# DigitalInclinometer.net
KiCad netlist of a schematic drawn in Altium Designer
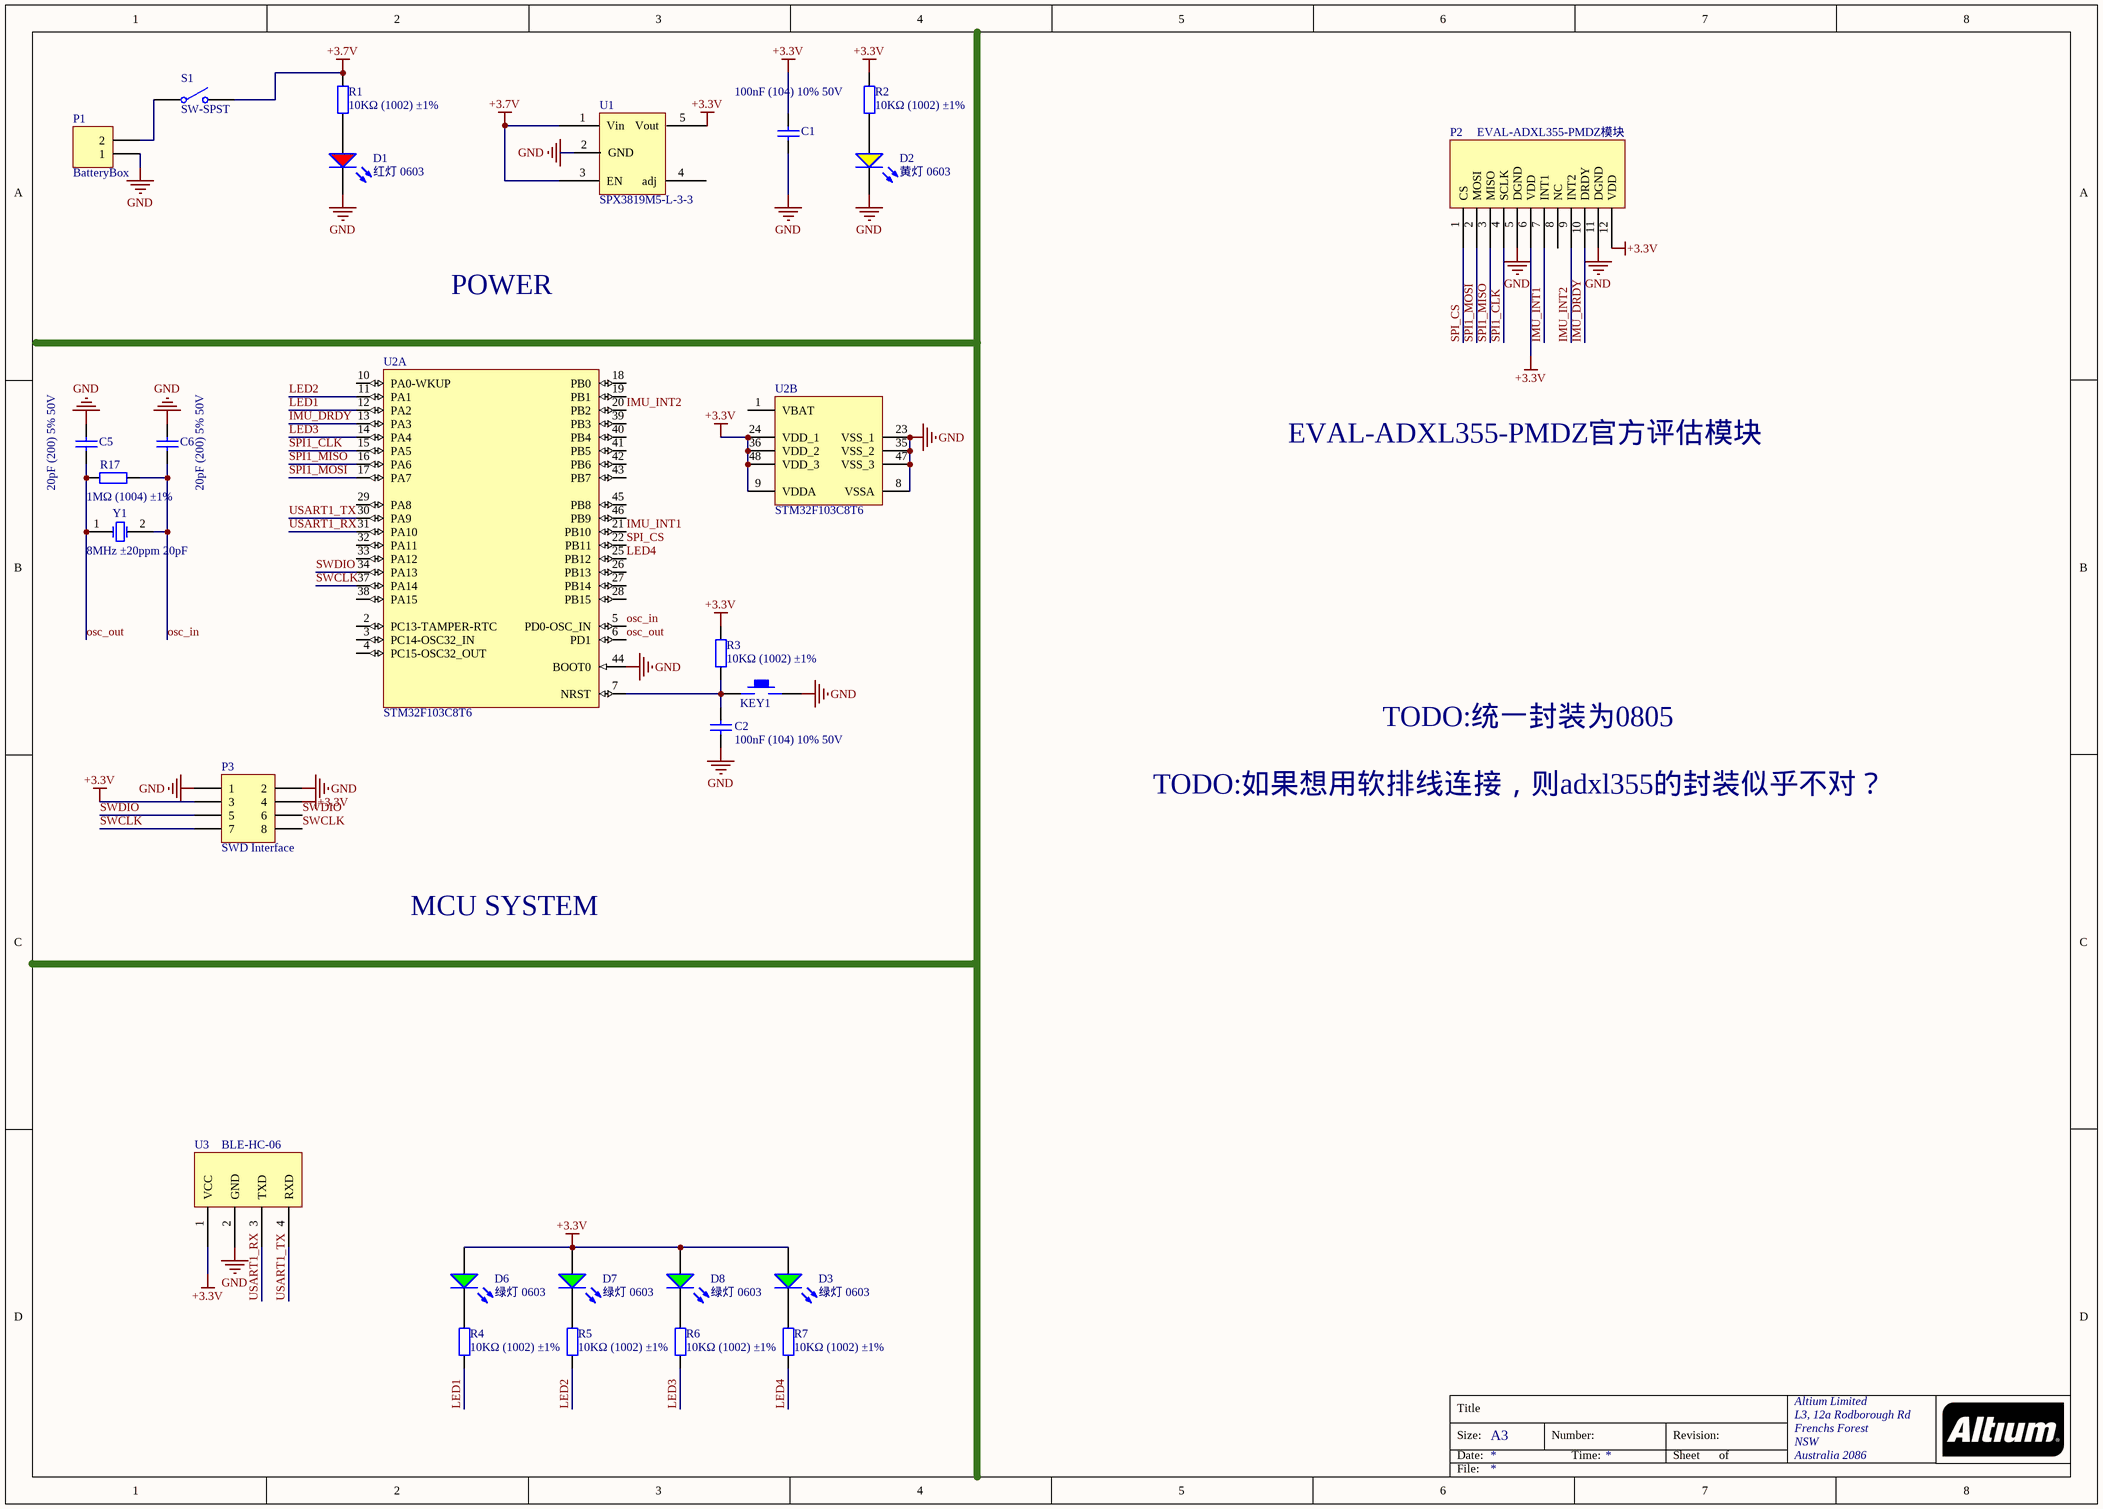
[diagram p0: DigitalInclinometer.SchDoc]

(export (version "E")
  (design (tool "Eeschema 10.0.6"))
  (components
    (comp (ref "C1")
      (value "100nF (104) 10% 50V")
      (footprint "0603_C")
      (description "贴片电容")
      (libsource (lib "Miscellaneous Devices LC") (part "0603 100nF (104) 10% 50V"))
    )
    (comp (ref "C2")
      (value "100nF (104) 10% 50V")
      (footprint "0603_C")
      (description "贴片电容")
      (libsource (lib "Miscellaneous Devices LC") (part "0603 100nF (104) 10% 50V"))
    )
    (comp (ref "C5")
      (value "20pF (200) 5% 50V")
      (footprint "0603_C")
      (description "贴片电容")
      (libsource (lib "Miscellaneous Devices LC") (part "0603 20pF (200) 5% 50V"))
    )
    (comp (ref "C6")
      (value "20pF (200) 5% 50V")
      (footprint "0603_C")
      (description "贴片电容")
      (libsource (lib "Miscellaneous Devices LC") (part "0603 20pF (200) 5% 50V"))
    )
    (comp (ref "D1")
      (value "红灯 0603")
      (footprint "0603_LED_S1")
      (description "发光二极管")
      (libsource (lib "Miscellaneous Devices LC") (part "0603 红灯"))
    )
    (comp (ref "D2")
      (value "黄灯 0603")
      (footprint "0603_LED_S1")
      (description "发光二极管")
      (libsource (lib "Miscellaneous Devices LC") (part "0603 黄灯"))
    )
    (comp (ref "D3")
      (value "绿灯 0603")
      (footprint "0603_LED_S1")
      (description "发光二极管")
      (libsource (lib "Miscellaneous Devices LC") (part "0603 绿灯"))
    )
    (comp (ref "D6")
      (value "绿灯 0603")
      (footprint "0603_LED_S1")
      (description "发光二极管")
      (libsource (lib "Miscellaneous Devices LC") (part "0603 绿灯"))
    )
    (comp (ref "D7")
      (value "绿灯 0603")
      (footprint "0603_LED_S1")
      (description "发光二极管")
      (libsource (lib "Miscellaneous Devices LC") (part "0603 绿灯"))
    )
    (comp (ref "D8")
      (value "绿灯 0603")
      (footprint "0603_LED_S1")
      (description "发光二极管")
      (libsource (lib "Miscellaneous Devices LC") (part "0603 绿灯"))
    )
    (comp (ref "KEY1")
      (value "KEY_M")
      (footprint "RESET-KEY-SMD")
      (libsource (lib "WarShip V3 STM32103封装库") (part "KEY_M"))
    )
    (comp (ref "P1")
      (value "BatteryBox")
      (footprint "14500LiBatteryBox")
      (description "Header, 2-Pin")
      (fields (field (name "PUBLISHER") "Altium Limited"))
      (libsource (lib "Miscellaneous Connectors") (part "Header 2"))
    )
    (comp (ref "P2")
      (value "EVAL-ADXL355-PMDZ模块")
      (footprint "ADXL355MODULE")
      (libsource (lib "IMU_STUDY") (part "EVAL-ADXL355-PMDZ模块"))
    )
    (comp (ref "P3")
      (value "SWD Interface")
      (footprint "2.54mmHeader2x4-SMD")
      (description "Header, 4-Pin, Dual row")
      (fields (field (name "PUBLISHER") "Altium Limited"))
      (libsource (lib "Miscellaneous Connectors") (part "Header 4X2"))
    )
    (comp (ref "R1")
      (value "10KΩ (1002) ±1%")
      (footprint "0603_R")
      (description "贴片电阻")
      (libsource (lib "Miscellaneous Devices LC") (part "0603 10KΩ (1002) 1%"))
    )
    (comp (ref "R2")
      (value "10KΩ (1002) ±1%")
      (footprint "0603_R")
      (description "贴片电阻")
      (libsource (lib "Miscellaneous Devices LC") (part "0603 10KΩ (1002) 1%"))
    )
    (comp (ref "R3")
      (value "10KΩ (1002) ±1%")
      (footprint "0603_R")
      (description "贴片电阻")
      (libsource (lib "Miscellaneous Devices LC") (part "0603 10KΩ (1002) 1%"))
    )
    (comp (ref "R4")
      (value "10KΩ (1002) ±1%")
      (footprint "0603_R")
      (description "贴片电阻")
      (libsource (lib "Miscellaneous Devices LC") (part "0603 10KΩ (1002) 1%"))
    )
    (comp (ref "R5")
      (value "10KΩ (1002) ±1%")
      (footprint "0603_R")
      (description "贴片电阻")
      (libsource (lib "Miscellaneous Devices LC") (part "0603 10KΩ (1002) 1%"))
    )
    (comp (ref "R6")
      (value "10KΩ (1002) ±1%")
      (footprint "0603_R")
      (description "贴片电阻")
      (libsource (lib "Miscellaneous Devices LC") (part "0603 10KΩ (1002) 1%"))
    )
    (comp (ref "R7")
      (value "10KΩ (1002) ±1%")
      (footprint "0603_R")
      (description "贴片电阻")
      (libsource (lib "Miscellaneous Devices LC") (part "0603 10KΩ (1002) 1%"))
    )
    (comp (ref "R17")
      (value "1MΩ (1004) ±1%")
      (footprint "0603_R")
      (description "贴片电阻")
      (libsource (lib "Miscellaneous Devices LC") (part "0603 1MΩ (1004) 1%"))
    )
    (comp (ref "S1")
      (value "SW-SPST")
      (footprint "PowerSwitcher")
      (description "Single-Pole, Single-Throw Switch")
      (fields (field (name "PUBLISHER") "Altium Limited"))
      (libsource (lib "Miscellaneous Devices") (part "SW-SPST"))
    )
    (comp (ref "U1")
      (value "SPX3819M5-L-3-3")
      (footprint "SOT-23-5")
      (libsource (lib "micro_driver_demo") (part "SPX3819M5-L-3-3"))
    )
    (comp (ref "U2")
      (value "STM32F103C8T6")
      (footprint "LQFP-48_7x7x05P")
      (description "ARM")
      (libsource (lib "Miscellaneous Devices LC") (part "STM32F103C8T6"))
    )
    (comp (ref "U3")
      (value "BLE-HC-06")
      (footprint "BLE-HC06-SMD")
      (libsource (lib "DigitalInclinometer") (part "BLE-HC-06"))
    )
    (comp (ref "Y1")
      (value "8MHz ±20ppm 20pF")
      (footprint "SMD-5032_2P")
      (description "贴片晶振")
      (libsource (lib "Miscellaneous Devices LC") (part "SMD-5032_2P 8MHz 20ppm 20pF"))
    )
  )
  (nets
    (net (code "1") (name "+3.3V") (class "Default")
      (node (ref "C1") (pin "2") (pinfunction "2_2") (pintype "passive"))
      (node (ref "D3") (pin "A") (pinfunction "A_A") (pintype "passive"))
      (node (ref "D6") (pin "A") (pinfunction "A_A") (pintype "passive"))
      (node (ref "D7") (pin "A") (pinfunction "A_A") (pintype "passive"))
      (node (ref "D8") (pin "A") (pinfunction "A_A") (pintype "passive"))
      (node (ref "P2") (pin "12") (pinfunction "VDD_12") (pintype "passive"))
      (node (ref "P2") (pin "6") (pinfunction "VDD_6") (pintype "passive"))
      (node (ref "P3") (pin "3") (pinfunction "3_3") (pintype "passive"))
      (node (ref "P3") (pin "4") (pinfunction "4_4") (pintype "passive"))
      (node (ref "R2") (pin "2") (pinfunction "2_2") (pintype "passive"))
      (node (ref "R3") (pin "2") (pinfunction "2_2") (pintype "passive"))
      (node (ref "U1") (pin "5") (pinfunction "Vout_5") (pintype "passive"))
      (node (ref "U2") (pin "24") (pinfunction "VDD_1_24") (pintype "power_in"))
      (node (ref "U2") (pin "36") (pinfunction "VDD_2_36") (pintype "power_in"))
      (node (ref "U2") (pin "48") (pinfunction "VDD_3_48") (pintype "power_in"))
      (node (ref "U2") (pin "9") (pinfunction "VDDA_9") (pintype "power_in"))
      (node (ref "U3") (pin "1") (pinfunction "VCC_1") (pintype "passive"))
    )
    (net (code "2") (name "+3.7V") (class "Default")
      (node (ref "R1") (pin "2") (pinfunction "2_2") (pintype "passive"))
      (node (ref "S1") (pin "2") (pinfunction "NO_2") (pintype "passive"))
      (node (ref "U1") (pin "1") (pinfunction "Vin_1") (pintype "passive"))
      (node (ref "U1") (pin "3") (pinfunction "EN_3") (pintype "passive"))
    )
    (net (code "3") (name "/IMU_DRDY") (class "Default")
      (node (ref "P2") (pin "10") (pinfunction "DRDY_10") (pintype "passive"))
      (node (ref "U2") (pin "13") (pinfunction "PA3_13") (pintype "bidirectional"))
    )
    (net (code "4") (name "/IMU_INT1") (class "Default")
      (node (ref "P2") (pin "7") (pinfunction "INT1_7") (pintype "passive"))
      (node (ref "U2") (pin "21") (pinfunction "PB10_21") (pintype "bidirectional"))
    )
    (net (code "5") (name "/IMU_INT2") (class "Default")
      (node (ref "P2") (pin "9") (pinfunction "INT2_9") (pintype "passive"))
      (node (ref "U2") (pin "20") (pinfunction "PB2_20") (pintype "bidirectional"))
    )
    (net (code "6") (name "/LED1") (class "Default")
      (node (ref "R4") (pin "1") (pinfunction "1_1") (pintype "passive"))
      (node (ref "U2") (pin "12") (pinfunction "PA2_12") (pintype "bidirectional"))
    )
    (net (code "7") (name "/LED2") (class "Default")
      (node (ref "R5") (pin "1") (pinfunction "1_1") (pintype "passive"))
      (node (ref "U2") (pin "11") (pinfunction "PA1_11") (pintype "bidirectional"))
    )
    (net (code "8") (name "/LED3") (class "Default")
      (node (ref "R6") (pin "1") (pinfunction "1_1") (pintype "passive"))
      (node (ref "U2") (pin "14") (pinfunction "PA4_14") (pintype "bidirectional"))
    )
    (net (code "9") (name "/LED4") (class "Default")
      (node (ref "R7") (pin "1") (pinfunction "1_1") (pintype "passive"))
      (node (ref "U2") (pin "25") (pinfunction "PB12_25") (pintype "bidirectional"))
    )
    (net (code "10") (name "/SPI1_CLK") (class "Default")
      (node (ref "P2") (pin "4") (pinfunction "SCLK_4") (pintype "passive"))
      (node (ref "U2") (pin "15") (pinfunction "PA5_15") (pintype "bidirectional"))
    )
    (net (code "11") (name "/SPI1_MISO") (class "Default")
      (node (ref "P2") (pin "3") (pinfunction "MISO_3") (pintype "passive"))
      (node (ref "U2") (pin "16") (pinfunction "PA6_16") (pintype "bidirectional"))
    )
    (net (code "12") (name "/SPI1_MOSI") (class "Default")
      (node (ref "P2") (pin "2") (pinfunction "MOSI_2") (pintype "passive"))
      (node (ref "U2") (pin "17") (pinfunction "PA7_17") (pintype "bidirectional"))
    )
    (net (code "13") (name "/SPI_CS") (class "Default")
      (node (ref "P2") (pin "1") (pinfunction "CS_1") (pintype "passive"))
      (node (ref "U2") (pin "22") (pinfunction "PB11_22") (pintype "bidirectional"))
    )
    (net (code "14") (name "/SWCLK") (class "Default")
      (node (ref "P3") (pin "7") (pinfunction "7_7") (pintype "passive"))
      (node (ref "P3") (pin "8") (pinfunction "8_8") (pintype "passive"))
      (node (ref "U2") (pin "37") (pinfunction "PA14_37") (pintype "bidirectional"))
    )
    (net (code "15") (name "/SWDIO") (class "Default")
      (node (ref "P3") (pin "5") (pinfunction "5_5") (pintype "passive"))
      (node (ref "P3") (pin "6") (pinfunction "6_6") (pintype "passive"))
      (node (ref "U2") (pin "34") (pinfunction "PA13_34") (pintype "bidirectional"))
    )
    (net (code "16") (name "/USART1_RX") (class "Default")
      (node (ref "U2") (pin "31") (pinfunction "PA10_31") (pintype "bidirectional"))
      (node (ref "U3") (pin "3") (pinfunction "TXD_3") (pintype "passive"))
    )
    (net (code "17") (name "/USART1_TX") (class "Default")
      (node (ref "U2") (pin "30") (pinfunction "PA9_30") (pintype "bidirectional"))
      (node (ref "U3") (pin "4") (pinfunction "RXD_4") (pintype "passive"))
    )
    (net (code "18") (name "/osc_in") (class "Default")
      (node (ref "C6") (pin "1") (pinfunction "1_1") (pintype "passive"))
      (node (ref "R17") (pin "1") (pinfunction "1_1") (pintype "passive"))
      (node (ref "U2") (pin "5") (pinfunction "PD0-OSC_IN_5") (pintype "bidirectional"))
      (node (ref "Y1") (pin "2") (pinfunction "OSC2_2") (pintype "passive"))
    )
    (net (code "19") (name "/osc_out") (class "Default")
      (node (ref "C5") (pin "1") (pinfunction "1_1") (pintype "passive"))
      (node (ref "R17") (pin "2") (pinfunction "2_2") (pintype "passive"))
      (node (ref "U2") (pin "6") (pinfunction "PD1_6") (pintype "bidirectional"))
      (node (ref "Y1") (pin "1") (pinfunction "OSC1_1") (pintype "passive"))
    )
    (net (code "20") (name "GND") (class "Default")
      (node (ref "C1") (pin "1") (pinfunction "1_1") (pintype "passive"))
      (node (ref "C2") (pin "1") (pinfunction "1_1") (pintype "passive"))
      (node (ref "C5") (pin "2") (pinfunction "2_2") (pintype "passive"))
      (node (ref "C6") (pin "2") (pinfunction "2_2") (pintype "passive"))
      (node (ref "D1") (pin "K") (pinfunction "K_K") (pintype "passive"))
      (node (ref "D2") (pin "K") (pinfunction "K_K") (pintype "passive"))
      (node (ref "KEY1") (pin "2") (pinfunction "2_2") (pintype "passive"))
      (node (ref "P1") (pin "1") (pinfunction "1_1") (pintype "passive"))
      (node (ref "P2") (pin "11") (pinfunction "DGND_11") (pintype "passive"))
      (node (ref "P2") (pin "5") (pinfunction "DGND_5") (pintype "passive"))
      (node (ref "P3") (pin "1") (pinfunction "1_1") (pintype "passive"))
      (node (ref "P3") (pin "2") (pinfunction "2_2") (pintype "passive"))
      (node (ref "U1") (pin "2") (pinfunction "GND_2") (pintype "passive"))
      (node (ref "U2") (pin "23") (pinfunction "VSS_1_23") (pintype "power_in"))
      (node (ref "U2") (pin "35") (pinfunction "VSS_2_35") (pintype "power_in"))
      (node (ref "U2") (pin "44") (pinfunction "BOOT0_44") (pintype "input"))
      (node (ref "U2") (pin "47") (pinfunction "VSS_3_47") (pintype "power_in"))
      (node (ref "U2") (pin "8") (pinfunction "VSSA_8") (pintype "power_in"))
      (node (ref "U3") (pin "2") (pinfunction "GND_2") (pintype "passive"))
    )
    (net (code "21") (name "Net-(D1-PadA)") (class "Default")
      (node (ref "D1") (pin "A") (pinfunction "A_A") (pintype "passive"))
      (node (ref "R1") (pin "1") (pinfunction "1_1") (pintype "passive"))
    )
    (net (code "22") (name "Net-(D2-PadA)") (class "Default")
      (node (ref "D2") (pin "A") (pinfunction "A_A") (pintype "passive"))
      (node (ref "R2") (pin "1") (pinfunction "1_1") (pintype "passive"))
    )
    (net (code "23") (name "Net-(D3-PadK)") (class "Default")
      (node (ref "D3") (pin "K") (pinfunction "K_K") (pintype "passive"))
      (node (ref "R7") (pin "2") (pinfunction "2_2") (pintype "passive"))
    )
    (net (code "24") (name "Net-(D6-PadK)") (class "Default")
      (node (ref "D6") (pin "K") (pinfunction "K_K") (pintype "passive"))
      (node (ref "R4") (pin "2") (pinfunction "2_2") (pintype "passive"))
    )
    (net (code "25") (name "Net-(D7-PadK)") (class "Default")
      (node (ref "D7") (pin "K") (pinfunction "K_K") (pintype "passive"))
      (node (ref "R5") (pin "2") (pinfunction "2_2") (pintype "passive"))
    )
    (net (code "26") (name "Net-(D8-PadK)") (class "Default")
      (node (ref "D8") (pin "K") (pinfunction "K_K") (pintype "passive"))
      (node (ref "R6") (pin "2") (pinfunction "2_2") (pintype "passive"))
    )
    (net (code "27") (name "Net-(S1-COMMON)") (class "Default")
      (node (ref "P1") (pin "2") (pinfunction "2_2") (pintype "passive"))
      (node (ref "S1") (pin "1") (pinfunction "COMMON_1") (pintype "passive"))
    )
    (net (code "28") (name "Net-(U2A-NRST)") (class "Default")
      (node (ref "C2") (pin "2") (pinfunction "2_2") (pintype "passive"))
      (node (ref "KEY1") (pin "1") (pinfunction "1_1") (pintype "passive"))
      (node (ref "R3") (pin "1") (pinfunction "1_1") (pintype "passive"))
      (node (ref "U2") (pin "7") (pinfunction "NRST_7") (pintype "bidirectional"))
    )
    (net (code "29") (name "unconnected-(P2-NC-Pad8)") (class "Default")
      (node (ref "P2") (pin "8") (pinfunction "NC_8") (pintype "passive"))
    )
    (net (code "30") (name "unconnected-(U1-adj-Pad4)") (class "Default")
      (node (ref "U1") (pin "4") (pinfunction "adj_4") (pintype "passive"))
    )
    (net (code "31") (name "unconnected-(U2A-PA0-WKUP-Pad10)") (class "Default")
      (node (ref "U2") (pin "10") (pinfunction "PA0-WKUP_10") (pintype "bidirectional"))
    )
    (net (code "32") (name "unconnected-(U2A-PA8-Pad29)") (class "Default")
      (node (ref "U2") (pin "29") (pinfunction "PA8_29") (pintype "bidirectional"))
    )
    (net (code "33") (name "unconnected-(U2A-PA11-Pad32)") (class "Default")
      (node (ref "U2") (pin "32") (pinfunction "PA11_32") (pintype "bidirectional"))
    )
    (net (code "34") (name "unconnected-(U2A-PA12-Pad33)") (class "Default")
      (node (ref "U2") (pin "33") (pinfunction "PA12_33") (pintype "bidirectional"))
    )
    (net (code "35") (name "unconnected-(U2A-PA15-Pad38)") (class "Default")
      (node (ref "U2") (pin "38") (pinfunction "PA15_38") (pintype "bidirectional"))
    )
    (net (code "36") (name "unconnected-(U2A-PB0-Pad18)") (class "Default")
      (node (ref "U2") (pin "18") (pinfunction "PB0_18") (pintype "bidirectional"))
    )
    (net (code "37") (name "unconnected-(U2A-PB1-Pad19)") (class "Default")
      (node (ref "U2") (pin "19") (pinfunction "PB1_19") (pintype "bidirectional"))
    )
    (net (code "38") (name "unconnected-(U2A-PB3-Pad39)") (class "Default")
      (node (ref "U2") (pin "39") (pinfunction "PB3_39") (pintype "bidirectional"))
    )
    (net (code "39") (name "unconnected-(U2A-PB4-Pad40)") (class "Default")
      (node (ref "U2") (pin "40") (pinfunction "PB4_40") (pintype "bidirectional"))
    )
    (net (code "40") (name "unconnected-(U2A-PB5-Pad41)") (class "Default")
      (node (ref "U2") (pin "41") (pinfunction "PB5_41") (pintype "bidirectional"))
    )
    (net (code "41") (name "unconnected-(U2A-PB6-Pad42)") (class "Default")
      (node (ref "U2") (pin "42") (pinfunction "PB6_42") (pintype "bidirectional"))
    )
    (net (code "42") (name "unconnected-(U2A-PB7-Pad43)") (class "Default")
      (node (ref "U2") (pin "43") (pinfunction "PB7_43") (pintype "bidirectional"))
    )
    (net (code "43") (name "unconnected-(U2A-PB8-Pad45)") (class "Default")
      (node (ref "U2") (pin "45") (pinfunction "PB8_45") (pintype "bidirectional"))
    )
    (net (code "44") (name "unconnected-(U2A-PB9-Pad46)") (class "Default")
      (node (ref "U2") (pin "46") (pinfunction "PB9_46") (pintype "bidirectional"))
    )
    (net (code "45") (name "unconnected-(U2A-PB13-Pad26)") (class "Default")
      (node (ref "U2") (pin "26") (pinfunction "PB13_26") (pintype "bidirectional"))
    )
    (net (code "46") (name "unconnected-(U2A-PB14-Pad27)") (class "Default")
      (node (ref "U2") (pin "27") (pinfunction "PB14_27") (pintype "bidirectional"))
    )
    (net (code "47") (name "unconnected-(U2A-PB15-Pad28)") (class "Default")
      (node (ref "U2") (pin "28") (pinfunction "PB15_28") (pintype "bidirectional"))
    )
    (net (code "48") (name "unconnected-(U2A-PC13-TAMPER-RTC-Pad2)") (class "Default")
      (node (ref "U2") (pin "2") (pinfunction "PC13-TAMPER-RTC_2") (pintype "bidirectional"))
    )
    (net (code "49") (name "unconnected-(U2A-PC14-OSC32_IN-Pad3)") (class "Default")
      (node (ref "U2") (pin "3") (pinfunction "PC14-OSC32_IN_3") (pintype "bidirectional"))
    )
    (net (code "50") (name "unconnected-(U2A-PC15-OSC32_OUT-Pad4)") (class "Default")
      (node (ref "U2") (pin "4") (pinfunction "PC15-OSC32_OUT_4") (pintype "bidirectional"))
    )
    (net (code "51") (name "unconnected-(U2B-VBAT-Pad1)") (class "Default")
      (node (ref "U2") (pin "1") (pinfunction "VBAT_1") (pintype "power_in"))
    )
  )
)
